# SCH_Business_Card_2024-01-29.net
KiCad netlist of a schematic drawn in EasyEDA
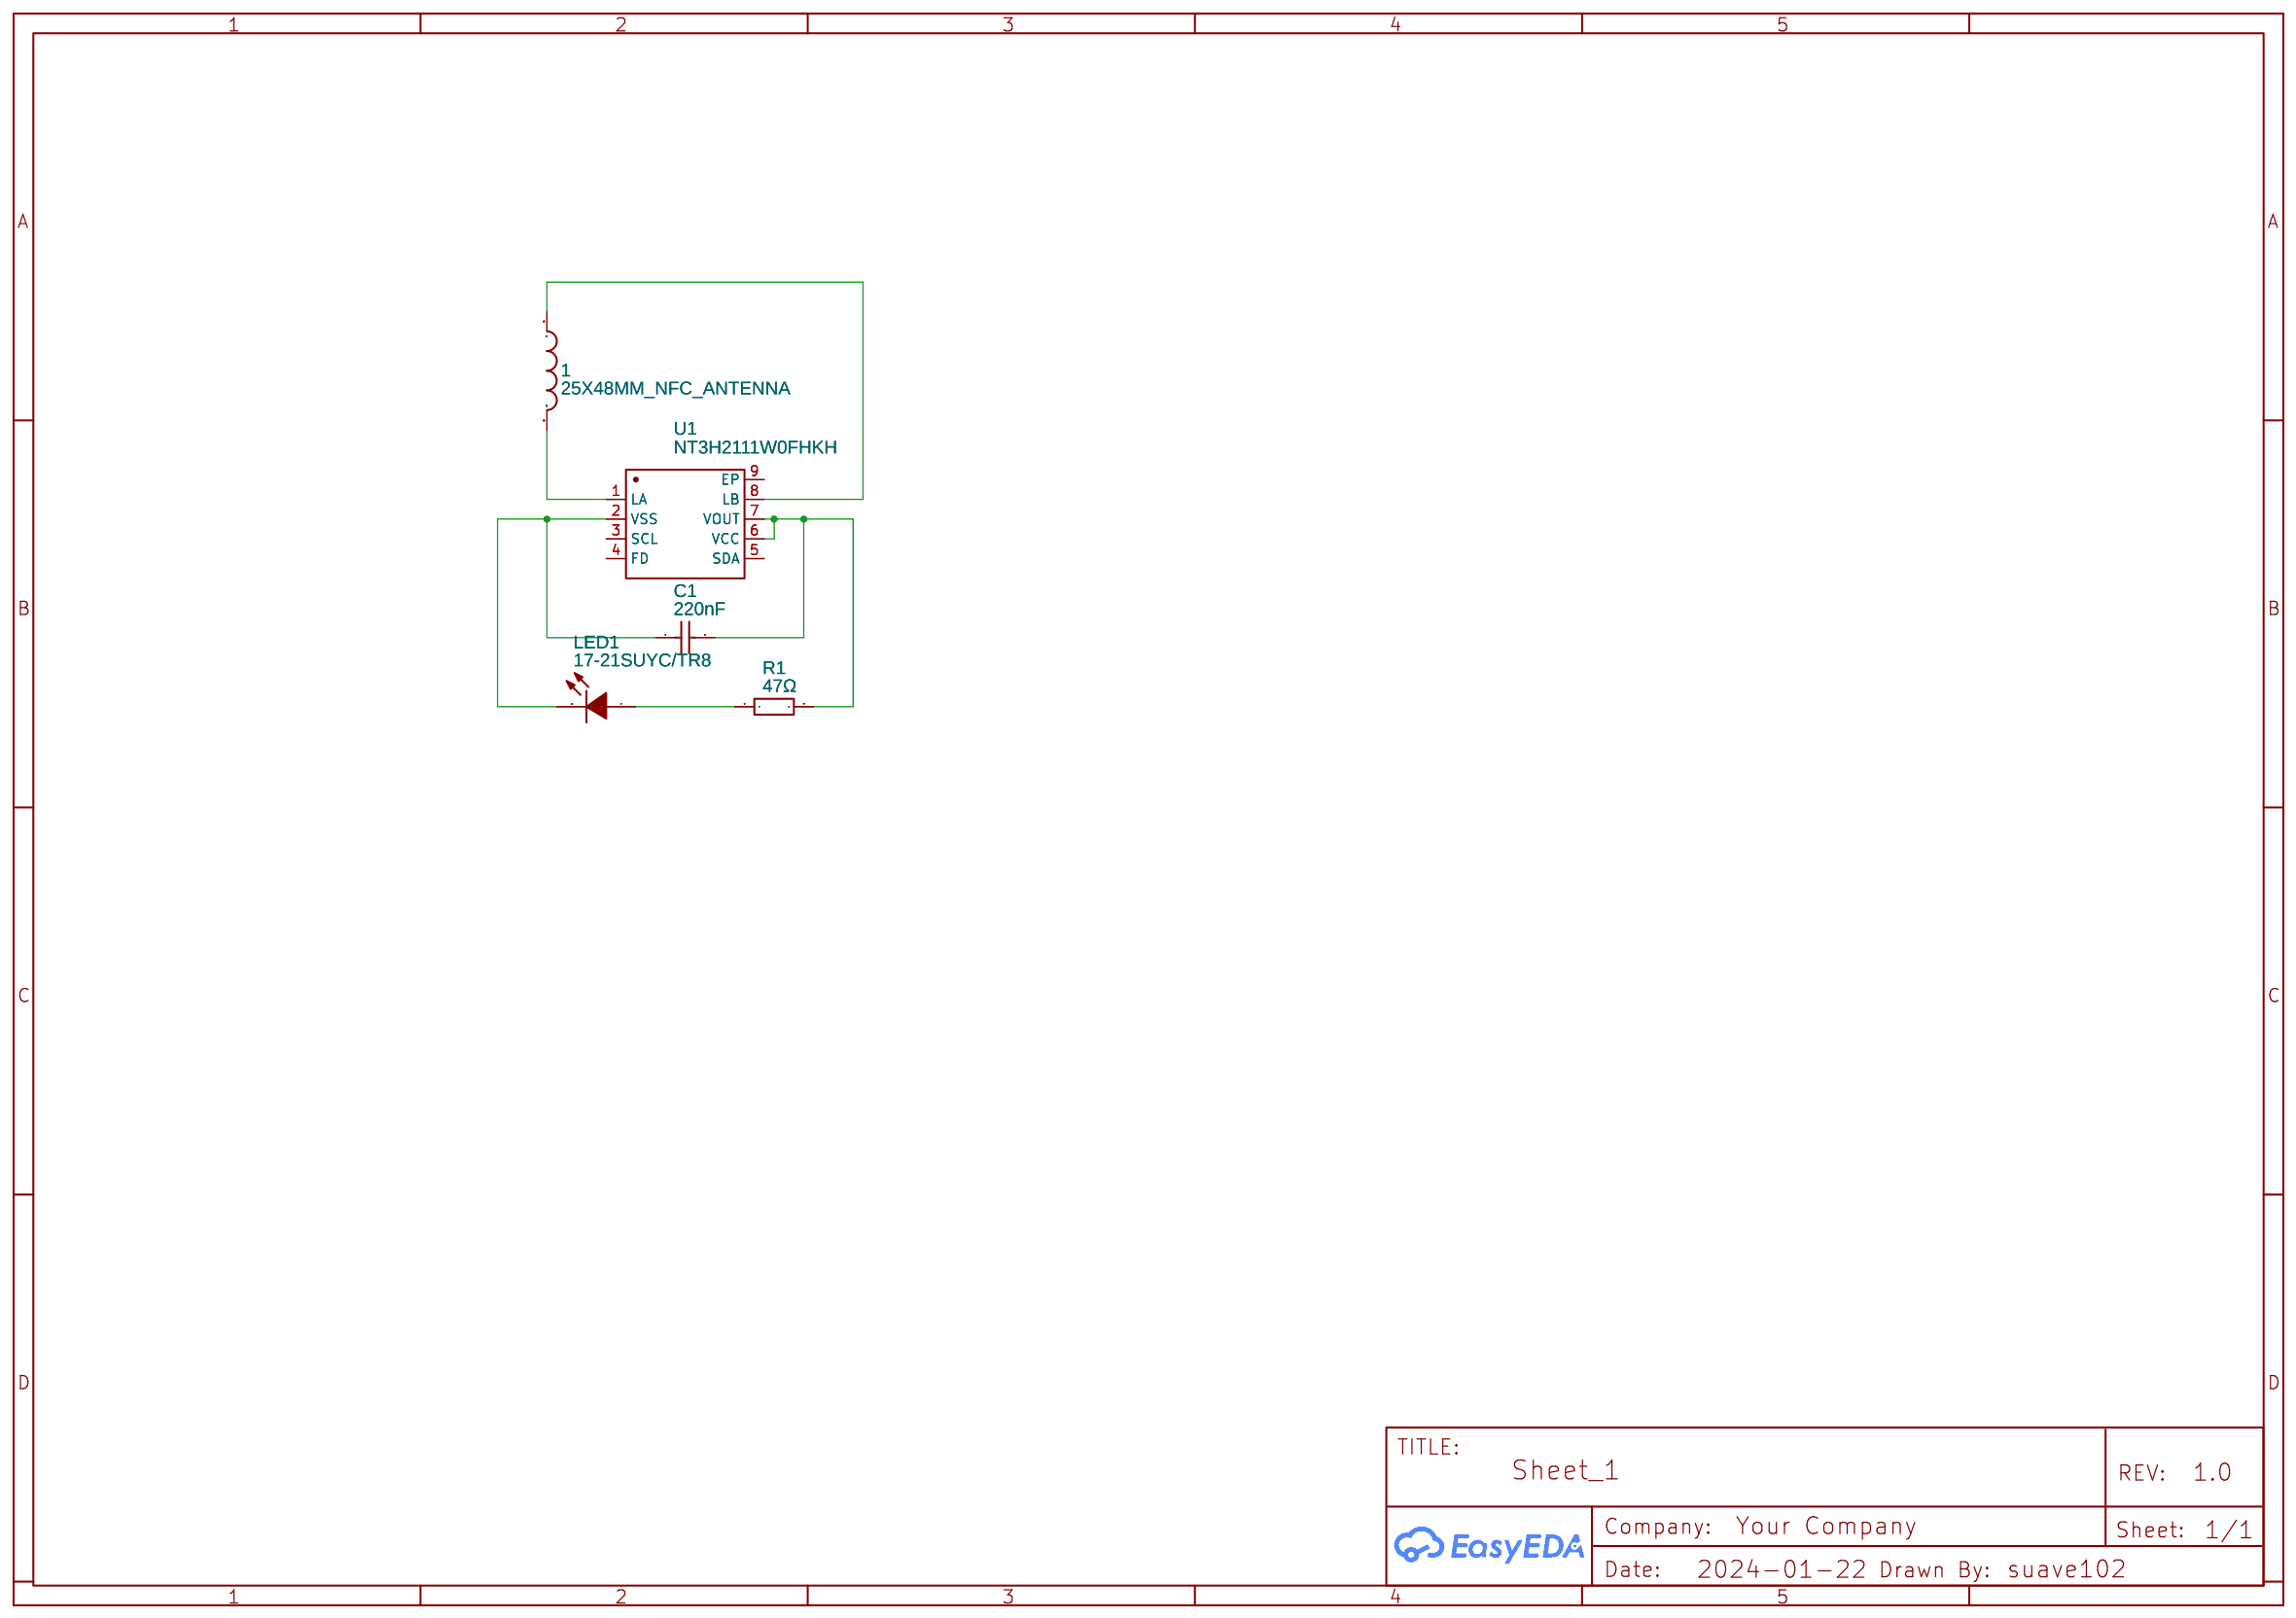
[diagram p0: schematic sheet]

(export (version "E")
  (design (tool "Eeschema 10.0.6"))
  (components
    (comp (ref "1") (value "25X48MM_NFC_ANTENNA") (libsource (lib "") (part "25X48MM_NFC_ANTENNA")))
    (comp (ref "C1")
      (value "220nF")
      (fields
        (field (name "Manufacturer Part") "CL10B224KA8NNNC")
        (field (name "Manufacturer") "SAMSUNG(三星)")
      )
      (libsource (lib "") (part "CL10B224KA8NNNC"))
    )
    (comp (ref "LED1")
      (value "17-21SUYC/TR8")
      (fields (field (name "Manufacturer Part") "KT-0805黄灯") (field (name "Manufacturer") "KENTO"))
      (libsource (lib "") (part "17-21SUYC/TR8"))
    )
    (comp (ref "R1")
      (value "47Ω")
      (fields
        (field (name "Manufacturer Part") "0603WAF470JT5E")
        (field (name "Manufacturer") "UNI-ROYAL(厚声)")
      )
      (libsource (lib "") (part "0603WAF470JT5E"))
    )
    (comp (ref "U1")
      (value "NT3H2111W0FHKH")
      (fields (field (name "Manufacturer") "NXP(恩智浦)"))
      (libsource (lib "") (part "NT3H2111W0FHKH"))
    )
  )
  (nets
    (net (code "1") (name "Net-(LED1-+)") (class "Default")
      (node (ref "LED1") (pin "1") (pinfunction "+_1") (pintype "unspecified"))
      (node (ref "R1") (pin "1") (pinfunction "1_1") (pintype "input"))
    )
    (net (code "2") (name "Net-(LED1--)") (class "Default")
      (node (ref "C1") (pin "1") (pinfunction "1_1") (pintype "input"))
      (node (ref "LED1") (pin "2") (pinfunction "-_2") (pintype "unspecified"))
      (node (ref "U1") (pin "2") (pinfunction "VSS_2") (pintype "unspecified"))
    )
    (net (code "3") (name "Net-(U1-LA)") (class "Default")
      (node (ref "1") (pin "P$2") (pinfunction "P$2_P$2") (pintype "bidirectional"))
      (node (ref "U1") (pin "1") (pinfunction "LA_1") (pintype "unspecified"))
    )
    (net (code "4") (name "Net-(U1-LB)") (class "Default")
      (node (ref "1") (pin "P$1") (pinfunction "P$1_P$1") (pintype "bidirectional"))
      (node (ref "U1") (pin "8") (pinfunction "LB_8") (pintype "unspecified"))
    )
    (net (code "5") (name "Net-(U1-VCC)") (class "Default")
      (node (ref "C1") (pin "2") (pinfunction "2_2") (pintype "input"))
      (node (ref "R1") (pin "2") (pinfunction "2_2") (pintype "input"))
      (node (ref "U1") (pin "6") (pinfunction "VCC_6") (pintype "unspecified"))
      (node (ref "U1") (pin "7") (pinfunction "VOUT_7") (pintype "unspecified"))
    )
    (net (code "6") (name "unconnected-(U1-EP-Pad9)") (class "Default")
      (node (ref "U1") (pin "9") (pinfunction "EP_9") (pintype "unspecified"))
    )
    (net (code "7") (name "unconnected-(U1-FD-Pad4)") (class "Default")
      (node (ref "U1") (pin "4") (pinfunction "FD_4") (pintype "unspecified"))
    )
    (net (code "8") (name "unconnected-(U1-SCL-Pad3)") (class "Default")
      (node (ref "U1") (pin "3") (pinfunction "SCL_3") (pintype "unspecified"))
    )
    (net (code "9") (name "unconnected-(U1-SDA-Pad5)") (class "Default")
      (node (ref "U1") (pin "5") (pinfunction "SDA_5") (pintype "unspecified"))
    )
  )
)
